# Arduino_MEGA_2560-Rev3.net
KiCad netlist of a schematic drawn in EAGLE
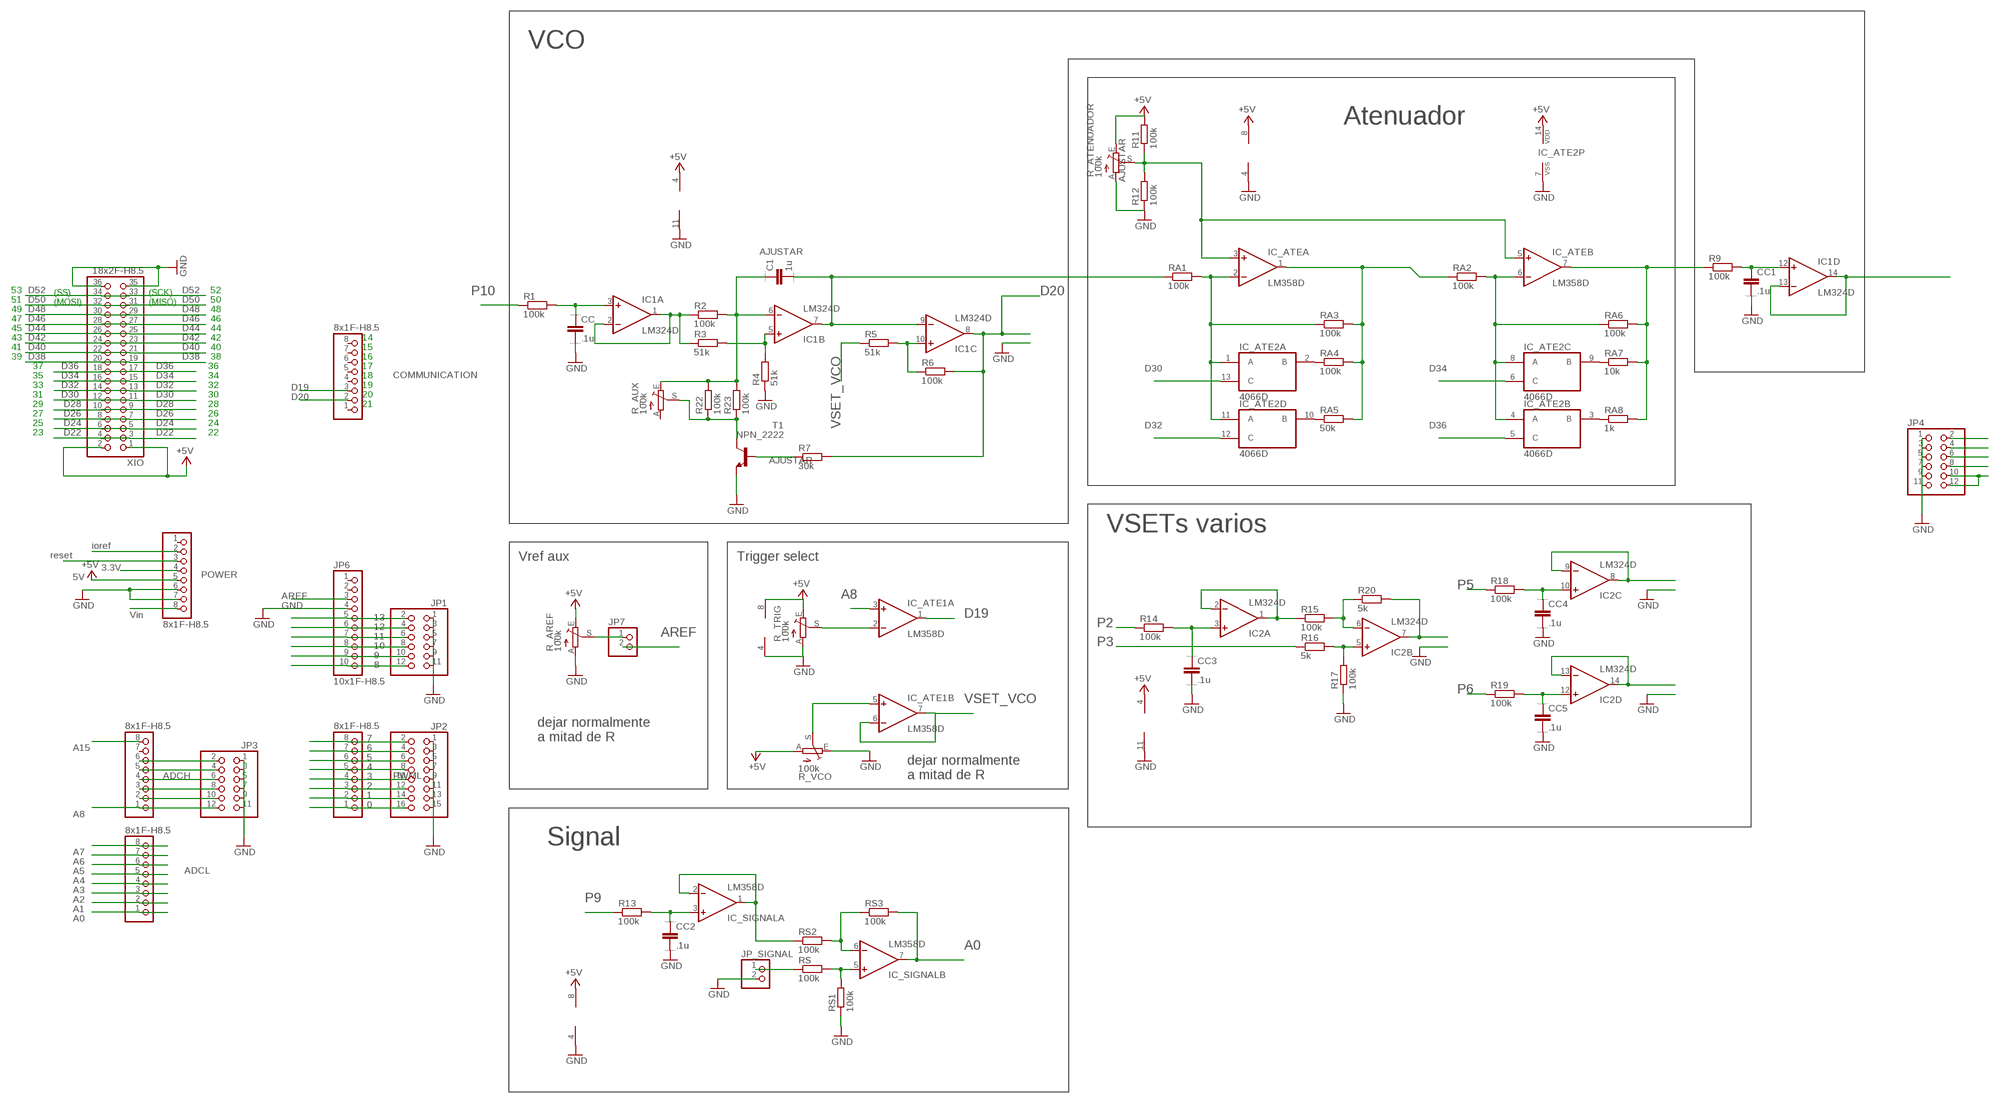
[diagram p0: schematic, sheet 1]

(export (version "E")
  (design (tool "Eeschema 10.0.6"))
  (components
    (comp (ref "ADCH")
      (value "8x1F-H8.5")
      (footprint "eagle-import:1X08")
      (libsource (lib "eagle-import") (part "PINHD-1X8"))
    )
    (comp (ref "ADCL")
      (value "8x1F-H8.5")
      (footprint "eagle-import:1X08")
      (libsource (lib "eagle-import") (part "PINHD-1X8"))
    )
    (comp (ref "C1")
      (value "1u")
      (footprint "eagle-import:C1812")
      (libsource (lib "eagle-import") (part "CC1812"))
    )
    (comp (ref "CC")
      (value ".1u")
      (footprint "eagle-import:C1812")
      (libsource (lib "eagle-import") (part "CC1812"))
    )
    (comp (ref "CC1")
      (value ".1u")
      (footprint "eagle-import:C1812")
      (libsource (lib "eagle-import") (part "CC1812"))
    )
    (comp (ref "CC2")
      (value ".1u")
      (footprint "eagle-import:C1812")
      (libsource (lib "eagle-import") (part "CC1812"))
    )
    (comp (ref "CC3")
      (value ".1u")
      (footprint "eagle-import:C1812")
      (libsource (lib "eagle-import") (part "CC1812"))
    )
    (comp (ref "CC4")
      (value ".1u")
      (footprint "eagle-import:C1812")
      (libsource (lib "eagle-import") (part "CC1812"))
    )
    (comp (ref "CC5")
      (value ".1u")
      (footprint "eagle-import:C1812")
      (libsource (lib "eagle-import") (part "CC1812"))
    )
    (comp (ref "COMMUNICATION")
      (value "8x1F-H8.5")
      (footprint "eagle-import:1X08")
      (libsource (lib "eagle-import") (part "PINHD-1X8"))
    )
    (comp (ref "IC1")
      (value "LM324D")
      (footprint "eagle-import:SO14")
      (libsource (lib "eagle-import") (part "LM324D"))
    )
    (comp (ref "IC2")
      (value "LM324D")
      (footprint "eagle-import:SO14")
      (libsource (lib "eagle-import") (part "LM324D"))
    )
    (comp (ref "IC_ATE")
      (value "LM358D")
      (footprint "eagle-import:SO08")
      (libsource (lib "eagle-import") (part "LM358D"))
    )
    (comp (ref "IC_ATE1")
      (value "LM358D")
      (footprint "eagle-import:SO08")
      (libsource (lib "eagle-import") (part "LM358D"))
    )
    (comp (ref "IC_ATE2")
      (value "4066D")
      (footprint "eagle-import:SO14")
      (libsource (lib "eagle-import") (part "4066D"))
    )
    (comp (ref "IC_SIGNAL")
      (value "LM358D")
      (footprint "eagle-import:SO08")
      (libsource (lib "eagle-import") (part "LM358D"))
    )
    (comp (ref "JP1")
      (value "PINHD-2X6")
      (footprint "eagle-import:2X06")
      (libsource (lib "eagle-import") (part "PINHD-2X6"))
    )
    (comp (ref "JP2")
      (value "PINHD-2X8")
      (footprint "eagle-import:2X08")
      (libsource (lib "eagle-import") (part "PINHD-2X8"))
    )
    (comp (ref "JP3")
      (value "PINHD-2X6")
      (footprint "eagle-import:2X06")
      (libsource (lib "eagle-import") (part "PINHD-2X6"))
    )
    (comp (ref "JP4")
      (value "PINHD-2X6")
      (footprint "eagle-import:2X06")
      (libsource (lib "eagle-import") (part "PINHD-2X6"))
    )
    (comp (ref "JP6")
      (value "10x1F-H8.5")
      (footprint "eagle-import:1X10")
      (libsource (lib "eagle-import") (part "PINHD-1X10_ARD"))
    )
    (comp (ref "JP7")
      (value "PINHD-1X2")
      (footprint "eagle-import:1X02")
      (libsource (lib "eagle-import") (part "PINHD-1X2"))
    )
    (comp (ref "JP_SIGNAL")
      (value "PINHD-1X2")
      (footprint "eagle-import:1X02")
      (libsource (lib "eagle-import") (part "PINHD-1X2"))
    )
    (comp (ref "POWER")
      (value "8x1F-H8.5")
      (footprint "eagle-import:1X08")
      (libsource (lib "eagle-import") (part "PINHD-1X8"))
    )
    (comp (ref "PWML")
      (value "8x1F-H8.5")
      (footprint "eagle-import:1X08")
      (libsource (lib "eagle-import") (part "PINHD-1X8"))
    )
    (comp (ref "R1")
      (value "100k")
      (footprint "eagle-import:R1206")
      (libsource (lib "eagle-import") (part "R-EU_R1206"))
    )
    (comp (ref "R2")
      (value "100k")
      (footprint "eagle-import:R1206")
      (libsource (lib "eagle-import") (part "R-EU_R1206"))
    )
    (comp (ref "R3")
      (value "51k")
      (footprint "eagle-import:R1206")
      (libsource (lib "eagle-import") (part "R-EU_R1206"))
    )
    (comp (ref "R4")
      (value "51k")
      (footprint "eagle-import:R1206")
      (libsource (lib "eagle-import") (part "R-EU_R1206"))
    )
    (comp (ref "R5")
      (value "51k")
      (footprint "eagle-import:R1206")
      (libsource (lib "eagle-import") (part "R-EU_R1206"))
    )
    (comp (ref "R6")
      (value "100k")
      (footprint "eagle-import:R1206")
      (libsource (lib "eagle-import") (part "R-EU_R1206"))
    )
    (comp (ref "R7")
      (value "30k")
      (footprint "eagle-import:0204_7")
      (libsource (lib "eagle-import") (part "R-EU_0204/7"))
    )
    (comp (ref "R9")
      (value "100k")
      (footprint "eagle-import:R1206")
      (libsource (lib "eagle-import") (part "R-EU_R1206"))
    )
    (comp (ref "R11")
      (value "100k")
      (footprint "eagle-import:R1206")
      (libsource (lib "eagle-import") (part "R-EU_R1206"))
    )
    (comp (ref "R12")
      (value "100k")
      (footprint "eagle-import:R1206")
      (libsource (lib "eagle-import") (part "R-EU_R1206"))
    )
    (comp (ref "R13")
      (value "100k")
      (footprint "eagle-import:R1206")
      (libsource (lib "eagle-import") (part "R-EU_R1206"))
    )
    (comp (ref "R14")
      (value "100k")
      (footprint "eagle-import:R1206")
      (libsource (lib "eagle-import") (part "R-EU_R1206"))
    )
    (comp (ref "R15")
      (value "100k")
      (footprint "eagle-import:R1206")
      (libsource (lib "eagle-import") (part "R-EU_R1206"))
    )
    (comp (ref "R16")
      (value "5k")
      (footprint "eagle-import:R1206")
      (libsource (lib "eagle-import") (part "R-EU_R1206"))
    )
    (comp (ref "R17")
      (value "100k")
      (footprint "eagle-import:R1206")
      (libsource (lib "eagle-import") (part "R-EU_R1206"))
    )
    (comp (ref "R18")
      (value "100k")
      (footprint "eagle-import:R1206")
      (libsource (lib "eagle-import") (part "R-EU_R1206"))
    )
    (comp (ref "R19")
      (value "100k")
      (footprint "eagle-import:R1206")
      (libsource (lib "eagle-import") (part "R-EU_R1206"))
    )
    (comp (ref "R20")
      (value "5k")
      (footprint "eagle-import:R1206")
      (libsource (lib "eagle-import") (part "R-EU_R1206"))
    )
    (comp (ref "R22")
      (value "100k")
      (footprint "eagle-import:R1206")
      (libsource (lib "eagle-import") (part "R-EU_R1206"))
    )
    (comp (ref "R23")
      (value "100k")
      (footprint "eagle-import:R1206")
      (libsource (lib "eagle-import") (part "R-EU_R1206"))
    )
    (comp (ref "RA1")
      (value "100k")
      (footprint "eagle-import:R1206")
      (libsource (lib "eagle-import") (part "R-EU_R1206"))
    )
    (comp (ref "RA2")
      (value "100k")
      (footprint "eagle-import:R1206")
      (libsource (lib "eagle-import") (part "R-EU_R1206"))
    )
    (comp (ref "RA3")
      (value "100k")
      (footprint "eagle-import:R1206")
      (libsource (lib "eagle-import") (part "R-EU_R1206"))
    )
    (comp (ref "RA4")
      (value "100k")
      (footprint "eagle-import:R1206")
      (libsource (lib "eagle-import") (part "R-EU_R1206"))
    )
    (comp (ref "RA5")
      (value "50k")
      (footprint "eagle-import:R1206")
      (libsource (lib "eagle-import") (part "R-EU_R1206"))
    )
    (comp (ref "RA6")
      (value "100k")
      (footprint "eagle-import:R1206")
      (libsource (lib "eagle-import") (part "R-EU_R1206"))
    )
    (comp (ref "RA7")
      (value "10k")
      (footprint "eagle-import:0204_7")
      (libsource (lib "eagle-import") (part "R-EU_0204/7"))
    )
    (comp (ref "RA8")
      (value "1k")
      (footprint "eagle-import:0204_7")
      (libsource (lib "eagle-import") (part "R-EU_0204/7"))
    )
    (comp (ref "RS")
      (value "100k")
      (footprint "eagle-import:R1206")
      (libsource (lib "eagle-import") (part "R-EU_R1206"))
    )
    (comp (ref "RS1")
      (value "100k")
      (footprint "eagle-import:R1206")
      (libsource (lib "eagle-import") (part "R-EU_R1206"))
    )
    (comp (ref "RS2")
      (value "100k")
      (footprint "eagle-import:R1206")
      (libsource (lib "eagle-import") (part "R-EU_R1206"))
    )
    (comp (ref "RS3")
      (value "100k")
      (footprint "eagle-import:R1206")
      (libsource (lib "eagle-import") (part "R-EU_R1206"))
    )
    (comp (ref "R_AREF")
      (value "100k")
      (footprint "eagle-import:B64Y")
      (libsource (lib "eagle-import") (part "TRIM_EU-B64Y"))
    )
    (comp (ref "R_ATENUADOR")
      (value "100k")
      (footprint "eagle-import:B64Y")
      (libsource (lib "eagle-import") (part "TRIM_EU-B64Y"))
    )
    (comp (ref "R_AUX")
      (value "100k")
      (footprint "eagle-import:B64Y")
      (libsource (lib "eagle-import") (part "TRIM_EU-B64Y"))
    )
    (comp (ref "R_TRIG")
      (value "100k")
      (footprint "eagle-import:B64Y")
      (libsource (lib "eagle-import") (part "TRIM_EU-B64Y"))
    )
    (comp (ref "R_VCO")
      (value "100k")
      (footprint "eagle-import:B64Y")
      (libsource (lib "eagle-import") (part "TRIM_EU-B64Y"))
    )
    (comp (ref "T1")
      (value "NPN_2222")
      (footprint "eagle-import:TO19_SUP")
      (libsource (lib "eagle-import") (part "NPN_SUP"))
    )
    (comp (ref "XIO")
      (value "18x2F-H8.5")
      (footprint "eagle-import:2X18")
      (libsource (lib "eagle-import") (part "PINHD-2X18"))
    )
  )
  (nets
    (net (code "1") (name "+5V") (class "Default")
      (node (ref "IC1") (pin "4") (pinfunction "V+_4") (pintype "power_in"))
      (node (ref "IC2") (pin "4") (pinfunction "V+_4") (pintype "power_in"))
      (node (ref "IC_ATE") (pin "8") (pinfunction "V+_8") (pintype "power_in"))
      (node (ref "IC_ATE1") (pin "8") (pinfunction "V+_8") (pintype "power_in"))
      (node (ref "IC_ATE2") (pin "14") (pinfunction "VDD_14") (pintype "power_in"))
      (node (ref "IC_SIGNAL") (pin "8") (pinfunction "V+_8") (pintype "power_in"))
      (node (ref "POWER") (pin "5") (pinfunction "5_5") (pintype "passive"))
      (node (ref "R11") (pin "2") (pinfunction "2_2") (pintype "passive"))
      (node (ref "R_AREF") (pin "E") (pinfunction "E_E") (pintype "passive"))
      (node (ref "R_ATENUADOR") (pin "E") (pinfunction "E_E") (pintype "passive"))
      (node (ref "R_TRIG") (pin "E") (pinfunction "E_E") (pintype "passive"))
      (node (ref "R_VCO") (pin "A") (pinfunction "A_A") (pintype "passive"))
      (node (ref "XIO") (pin "1") (pinfunction "1_1") (pintype "passive"))
      (node (ref "XIO") (pin "2") (pinfunction "2_2") (pintype "passive"))
    )
    (net (code "2") (name "/A0") (class "Default")
      (node (ref "ADCL") (pin "1") (pinfunction "1_1") (pintype "passive"))
      (node (ref "IC_SIGNAL") (pin "7") (pinfunction "OUT_7") (pintype "output"))
      (node (ref "RS3") (pin "2") (pinfunction "2_2") (pintype "passive"))
    )
    (net (code "3") (name "/A8") (class "Default")
      (node (ref "ADCH") (pin "1") (pinfunction "1_1") (pintype "passive"))
      (node (ref "IC_ATE1") (pin "3") (pinfunction "+IN_3") (pintype "input"))
      (node (ref "JP3") (pin "12") (pinfunction "12_12") (pintype "passive"))
    )
    (net (code "4") (name "/AREF") (class "Default")
      (node (ref "JP6") (pin "3") (pinfunction "3_3") (pintype "passive"))
      (node (ref "JP7") (pin "2") (pinfunction "2_2") (pintype "passive"))
    )
    (net (code "5") (name "/D19") (class "Default")
      (node (ref "COMMUNICATION") (pin "3") (pinfunction "3_3") (pintype "passive"))
      (node (ref "IC_ATE1") (pin "1") (pinfunction "OUT_1") (pintype "output"))
    )
    (net (code "6") (name "/D20") (class "Default")
      (node (ref "COMMUNICATION") (pin "2") (pinfunction "2_2") (pintype "passive"))
      (node (ref "IC1") (pin "8") (pinfunction "OUT_8") (pintype "output"))
      (node (ref "JP4") (pin "2") (pinfunction "2_2") (pintype "passive"))
      (node (ref "R6") (pin "2") (pinfunction "2_2") (pintype "passive"))
      (node (ref "R7") (pin "2") (pinfunction "2_2") (pintype "passive"))
    )
    (net (code "7") (name "/D22") (class "Default")
      (node (ref "XIO") (pin "3") (pinfunction "3_3") (pintype "passive"))
      (node (ref "XIO") (pin "4") (pinfunction "4_4") (pintype "passive"))
    )
    (net (code "8") (name "/D24") (class "Default")
      (node (ref "XIO") (pin "5") (pinfunction "5_5") (pintype "passive"))
      (node (ref "XIO") (pin "6") (pinfunction "6_6") (pintype "passive"))
    )
    (net (code "9") (name "/D26") (class "Default")
      (node (ref "XIO") (pin "7") (pinfunction "7_7") (pintype "passive"))
      (node (ref "XIO") (pin "8") (pinfunction "8_8") (pintype "passive"))
    )
    (net (code "10") (name "/D28") (class "Default")
      (node (ref "XIO") (pin "10") (pinfunction "10_10") (pintype "passive"))
      (node (ref "XIO") (pin "9") (pinfunction "9_9") (pintype "passive"))
    )
    (net (code "11") (name "/D30") (class "Default")
      (node (ref "IC_ATE2") (pin "13") (pinfunction "C_13") (pintype "input"))
      (node (ref "XIO") (pin "11") (pinfunction "11_11") (pintype "passive"))
      (node (ref "XIO") (pin "12") (pinfunction "12_12") (pintype "passive"))
    )
    (net (code "12") (name "/D32") (class "Default")
      (node (ref "IC_ATE2") (pin "12") (pinfunction "C_12") (pintype "input"))
      (node (ref "XIO") (pin "13") (pinfunction "13_13") (pintype "passive"))
      (node (ref "XIO") (pin "14") (pinfunction "14_14") (pintype "passive"))
    )
    (net (code "13") (name "/D34") (class "Default")
      (node (ref "IC_ATE2") (pin "6") (pinfunction "C_6") (pintype "input"))
      (node (ref "XIO") (pin "15") (pinfunction "15_15") (pintype "passive"))
      (node (ref "XIO") (pin "16") (pinfunction "16_16") (pintype "passive"))
    )
    (net (code "14") (name "/D36") (class "Default")
      (node (ref "IC_ATE2") (pin "5") (pinfunction "C_5") (pintype "input"))
      (node (ref "XIO") (pin "17") (pinfunction "17_17") (pintype "passive"))
      (node (ref "XIO") (pin "18") (pinfunction "18_18") (pintype "passive"))
    )
    (net (code "15") (name "/D38") (class "Default")
      (node (ref "XIO") (pin "19") (pinfunction "19_19") (pintype "passive"))
      (node (ref "XIO") (pin "20") (pinfunction "20_20") (pintype "passive"))
    )
    (net (code "16") (name "/D40") (class "Default")
      (node (ref "XIO") (pin "21") (pinfunction "21_21") (pintype "passive"))
      (node (ref "XIO") (pin "22") (pinfunction "22_22") (pintype "passive"))
    )
    (net (code "17") (name "/D42") (class "Default")
      (node (ref "XIO") (pin "23") (pinfunction "23_23") (pintype "passive"))
      (node (ref "XIO") (pin "24") (pinfunction "24_24") (pintype "passive"))
    )
    (net (code "18") (name "/D44") (class "Default")
      (node (ref "XIO") (pin "25") (pinfunction "25_25") (pintype "passive"))
      (node (ref "XIO") (pin "26") (pinfunction "26_26") (pintype "passive"))
    )
    (net (code "19") (name "/D46") (class "Default")
      (node (ref "XIO") (pin "27") (pinfunction "27_27") (pintype "passive"))
      (node (ref "XIO") (pin "28") (pinfunction "28_28") (pintype "passive"))
    )
    (net (code "20") (name "/D48") (class "Default")
      (node (ref "XIO") (pin "29") (pinfunction "29_29") (pintype "passive"))
      (node (ref "XIO") (pin "30") (pinfunction "30_30") (pintype "passive"))
    )
    (net (code "21") (name "/D50") (class "Default")
      (node (ref "XIO") (pin "31") (pinfunction "31_31") (pintype "passive"))
      (node (ref "XIO") (pin "32") (pinfunction "32_32") (pintype "passive"))
    )
    (net (code "22") (name "/D52") (class "Default")
      (node (ref "XIO") (pin "33") (pinfunction "33_33") (pintype "passive"))
      (node (ref "XIO") (pin "34") (pinfunction "34_34") (pintype "passive"))
    )
    (net (code "23") (name "/P2") (class "Default")
      (node (ref "JP2") (pin "12") (pinfunction "12_12") (pintype "passive"))
      (node (ref "PWML") (pin "3") (pinfunction "3_3") (pintype "passive"))
      (node (ref "R14") (pin "1") (pinfunction "1_1") (pintype "passive"))
    )
    (net (code "24") (name "/P3") (class "Default")
      (node (ref "JP2") (pin "10") (pinfunction "10_10") (pintype "passive"))
      (node (ref "PWML") (pin "4") (pinfunction "4_4") (pintype "passive"))
      (node (ref "R16") (pin "1") (pinfunction "1_1") (pintype "passive"))
    )
    (net (code "25") (name "/P5") (class "Default")
      (node (ref "JP2") (pin "6") (pinfunction "6_6") (pintype "passive"))
      (node (ref "PWML") (pin "6") (pinfunction "6_6") (pintype "passive"))
      (node (ref "R18") (pin "1") (pinfunction "1_1") (pintype "passive"))
    )
    (net (code "26") (name "/P6") (class "Default")
      (node (ref "JP2") (pin "4") (pinfunction "4_4") (pintype "passive"))
      (node (ref "PWML") (pin "7") (pinfunction "7_7") (pintype "passive"))
      (node (ref "R19") (pin "1") (pinfunction "1_1") (pintype "passive"))
    )
    (net (code "27") (name "/P9") (class "Default")
      (node (ref "JP1") (pin "10") (pinfunction "10_10") (pintype "passive"))
      (node (ref "JP6") (pin "9") (pinfunction "9_9") (pintype "passive"))
      (node (ref "R13") (pin "1") (pinfunction "1_1") (pintype "passive"))
    )
    (net (code "28") (name "/P10") (class "Default")
      (node (ref "JP1") (pin "8") (pinfunction "8_8") (pintype "passive"))
      (node (ref "JP6") (pin "8") (pinfunction "8_8") (pintype "passive"))
      (node (ref "R1") (pin "1") (pinfunction "1_1") (pintype "passive"))
    )
    (net (code "29") (name "/SP5") (class "Default")
      (node (ref "IC2") (pin "8") (pinfunction "OUT_8") (pintype "output"))
      (node (ref "IC2") (pin "9") (pinfunction "-IN_9") (pintype "input"))
      (node (ref "JP4") (pin "4") (pinfunction "4_4") (pintype "passive"))
    )
    (net (code "30") (name "/SP6") (class "Default")
      (node (ref "IC2") (pin "13") (pinfunction "-IN_13") (pintype "input"))
      (node (ref "IC2") (pin "14") (pinfunction "OUT_14") (pintype "output"))
      (node (ref "JP4") (pin "6") (pinfunction "6_6") (pintype "passive"))
    )
    (net (code "31") (name "/SPSUPER") (class "Default")
      (node (ref "IC2") (pin "7") (pinfunction "OUT_7") (pintype "output"))
      (node (ref "JP4") (pin "8") (pinfunction "8_8") (pintype "passive"))
      (node (ref "R20") (pin "2") (pinfunction "2_2") (pintype "passive"))
    )
    (net (code "32") (name "/TRIANG_ATE") (class "Default")
      (node (ref "IC1") (pin "13") (pinfunction "-IN_13") (pintype "input"))
      (node (ref "IC1") (pin "14") (pinfunction "OUT_14") (pintype "output"))
      (node (ref "JP4") (pin "10") (pinfunction "10_10") (pintype "passive"))
      (node (ref "JP4") (pin "12") (pinfunction "12_12") (pintype "passive"))
    )
    (net (code "33") (name "/VSET_VCO") (class "Default")
      (node (ref "IC_ATE1") (pin "6") (pinfunction "-IN_6") (pintype "input"))
      (node (ref "IC_ATE1") (pin "7") (pinfunction "OUT_7") (pintype "output"))
      (node (ref "R5") (pin "1") (pinfunction "1_1") (pintype "passive"))
    )
    (net (code "34") (name "GND") (class "Default")
      (node (ref "CC") (pin "2") (pinfunction "2_2") (pintype "passive"))
      (node (ref "CC1") (pin "2") (pinfunction "2_2") (pintype "passive"))
      (node (ref "CC2") (pin "2") (pinfunction "2_2") (pintype "passive"))
      (node (ref "CC3") (pin "2") (pinfunction "2_2") (pintype "passive"))
      (node (ref "CC4") (pin "2") (pinfunction "2_2") (pintype "passive"))
      (node (ref "CC5") (pin "2") (pinfunction "2_2") (pintype "passive"))
      (node (ref "IC1") (pin "11") (pinfunction "V-_11") (pintype "power_in"))
      (node (ref "IC2") (pin "11") (pinfunction "V-_11") (pintype "power_in"))
      (node (ref "IC_ATE") (pin "4") (pinfunction "V-_4") (pintype "power_in"))
      (node (ref "IC_ATE1") (pin "4") (pinfunction "V-_4") (pintype "power_in"))
      (node (ref "IC_ATE2") (pin "7") (pinfunction "VSS_7") (pintype "power_in"))
      (node (ref "IC_SIGNAL") (pin "4") (pinfunction "V-_4") (pintype "power_in"))
      (node (ref "JP1") (pin "1") (pinfunction "1_1") (pintype "passive"))
      (node (ref "JP1") (pin "11") (pinfunction "11_11") (pintype "passive"))
      (node (ref "JP1") (pin "3") (pinfunction "3_3") (pintype "passive"))
      (node (ref "JP1") (pin "5") (pinfunction "5_5") (pintype "passive"))
      (node (ref "JP1") (pin "7") (pinfunction "7_7") (pintype "passive"))
      (node (ref "JP1") (pin "9") (pinfunction "9_9") (pintype "passive"))
      (node (ref "JP2") (pin "1") (pinfunction "1_1") (pintype "passive"))
      (node (ref "JP2") (pin "11") (pinfunction "11_11") (pintype "passive"))
      (node (ref "JP2") (pin "13") (pinfunction "13_13") (pintype "passive"))
      (node (ref "JP2") (pin "15") (pinfunction "15_15") (pintype "passive"))
      (node (ref "JP2") (pin "3") (pinfunction "3_3") (pintype "passive"))
      (node (ref "JP2") (pin "5") (pinfunction "5_5") (pintype "passive"))
      (node (ref "JP2") (pin "7") (pinfunction "7_7") (pintype "passive"))
      (node (ref "JP2") (pin "9") (pinfunction "9_9") (pintype "passive"))
      (node (ref "JP3") (pin "1") (pinfunction "1_1") (pintype "passive"))
      (node (ref "JP3") (pin "11") (pinfunction "11_11") (pintype "passive"))
      (node (ref "JP3") (pin "3") (pinfunction "3_3") (pintype "passive"))
      (node (ref "JP3") (pin "5") (pinfunction "5_5") (pintype "passive"))
      (node (ref "JP3") (pin "7") (pinfunction "7_7") (pintype "passive"))
      (node (ref "JP3") (pin "9") (pinfunction "9_9") (pintype "passive"))
      (node (ref "JP4") (pin "1") (pinfunction "1_1") (pintype "passive"))
      (node (ref "JP4") (pin "11") (pinfunction "11_11") (pintype "passive"))
      (node (ref "JP4") (pin "3") (pinfunction "3_3") (pintype "passive"))
      (node (ref "JP4") (pin "5") (pinfunction "5_5") (pintype "passive"))
      (node (ref "JP4") (pin "7") (pinfunction "7_7") (pintype "passive"))
      (node (ref "JP4") (pin "9") (pinfunction "9_9") (pintype "passive"))
      (node (ref "JP6") (pin "4") (pinfunction "4_4") (pintype "passive"))
      (node (ref "JP_SIGNAL") (pin "2") (pinfunction "2_2") (pintype "passive"))
      (node (ref "POWER") (pin "6") (pinfunction "6_6") (pintype "passive"))
      (node (ref "POWER") (pin "7") (pinfunction "7_7") (pintype "passive"))
      (node (ref "R12") (pin "1") (pinfunction "1_1") (pintype "passive"))
      (node (ref "R17") (pin "1") (pinfunction "1_1") (pintype "passive"))
      (node (ref "R4") (pin "1") (pinfunction "1_1") (pintype "passive"))
      (node (ref "RS1") (pin "1") (pinfunction "1_1") (pintype "passive"))
      (node (ref "R_AREF") (pin "A") (pinfunction "A_A") (pintype "passive"))
      (node (ref "R_ATENUADOR") (pin "A") (pinfunction "A_A") (pintype "passive"))
      (node (ref "R_TRIG") (pin "A") (pinfunction "A_A") (pintype "passive"))
      (node (ref "R_VCO") (pin "E") (pinfunction "E_E") (pintype "passive"))
      (node (ref "T1") (pin "3") (pinfunction "E_3") (pintype "passive"))
      (node (ref "XIO") (pin "35") (pinfunction "35_35") (pintype "passive"))
      (node (ref "XIO") (pin "36") (pinfunction "36_36") (pintype "passive"))
    )
    (net (code "35") (name "Net-(ADCH-Pad2)") (class "Default")
      (node (ref "ADCH") (pin "2") (pinfunction "2_2") (pintype "passive"))
      (node (ref "JP3") (pin "10") (pinfunction "10_10") (pintype "passive"))
    )
    (net (code "36") (name "Net-(ADCH-Pad3)") (class "Default")
      (node (ref "ADCH") (pin "3") (pinfunction "3_3") (pintype "passive"))
      (node (ref "JP3") (pin "8") (pinfunction "8_8") (pintype "passive"))
    )
    (net (code "37") (name "Net-(ADCH-Pad4)") (class "Default")
      (node (ref "ADCH") (pin "4") (pinfunction "4_4") (pintype "passive"))
      (node (ref "JP3") (pin "6") (pinfunction "6_6") (pintype "passive"))
    )
    (net (code "38") (name "Net-(ADCH-Pad5)") (class "Default")
      (node (ref "ADCH") (pin "5") (pinfunction "5_5") (pintype "passive"))
      (node (ref "JP3") (pin "4") (pinfunction "4_4") (pintype "passive"))
    )
    (net (code "39") (name "Net-(ADCH-Pad6)") (class "Default")
      (node (ref "ADCH") (pin "6") (pinfunction "6_6") (pintype "passive"))
      (node (ref "JP3") (pin "2") (pinfunction "2_2") (pintype "passive"))
    )
    (net (code "40") (name "Net-(IC1A-+IN)") (class "Default")
      (node (ref "CC") (pin "1") (pinfunction "1_1") (pintype "passive"))
      (node (ref "IC1") (pin "3") (pinfunction "+IN_3") (pintype "input"))
      (node (ref "R1") (pin "2") (pinfunction "2_2") (pintype "passive"))
    )
    (net (code "41") (name "Net-(IC1A--IN)") (class "Default")
      (node (ref "IC1") (pin "1") (pinfunction "OUT_1") (pintype "output"))
      (node (ref "IC1") (pin "2") (pinfunction "-IN_2") (pintype "input"))
      (node (ref "R2") (pin "1") (pinfunction "1_1") (pintype "passive"))
      (node (ref "R3") (pin "1") (pinfunction "1_1") (pintype "passive"))
    )
    (net (code "42") (name "Net-(IC1B-+IN)") (class "Default")
      (node (ref "IC1") (pin "5") (pinfunction "+IN_5") (pintype "input"))
      (node (ref "R3") (pin "2") (pinfunction "2_2") (pintype "passive"))
      (node (ref "R4") (pin "2") (pinfunction "2_2") (pintype "passive"))
    )
    (net (code "43") (name "Net-(IC1B--IN)") (class "Default")
      (node (ref "C1") (pin "1") (pinfunction "1_1") (pintype "passive"))
      (node (ref "IC1") (pin "6") (pinfunction "-IN_6") (pintype "input"))
      (node (ref "R2") (pin "2") (pinfunction "2_2") (pintype "passive"))
      (node (ref "R22") (pin "2") (pinfunction "2_2") (pintype "passive"))
      (node (ref "R23") (pin "2") (pinfunction "2_2") (pintype "passive"))
      (node (ref "R_AUX") (pin "E") (pinfunction "E_E") (pintype "passive"))
    )
    (net (code "44") (name "Net-(IC1B-OUT)") (class "Default")
      (node (ref "C1") (pin "2") (pinfunction "2_2") (pintype "passive"))
      (node (ref "IC1") (pin "7") (pinfunction "OUT_7") (pintype "output"))
      (node (ref "IC1") (pin "9") (pinfunction "-IN_9") (pintype "input"))
      (node (ref "RA1") (pin "1") (pinfunction "1_1") (pintype "passive"))
    )
    (net (code "45") (name "Net-(IC1C-+IN)") (class "Default")
      (node (ref "IC1") (pin "10") (pinfunction "+IN_10") (pintype "input"))
      (node (ref "R5") (pin "2") (pinfunction "2_2") (pintype "passive"))
      (node (ref "R6") (pin "1") (pinfunction "1_1") (pintype "passive"))
    )
    (net (code "46") (name "Net-(IC1D-+IN)") (class "Default")
      (node (ref "CC1") (pin "1") (pinfunction "1_1") (pintype "passive"))
      (node (ref "IC1") (pin "12") (pinfunction "+IN_12") (pintype "input"))
      (node (ref "R9") (pin "2") (pinfunction "2_2") (pintype "passive"))
    )
    (net (code "47") (name "Net-(IC2A-+IN)") (class "Default")
      (node (ref "CC3") (pin "1") (pinfunction "1_1") (pintype "passive"))
      (node (ref "IC2") (pin "3") (pinfunction "+IN_3") (pintype "input"))
      (node (ref "R14") (pin "2") (pinfunction "2_2") (pintype "passive"))
    )
    (net (code "48") (name "Net-(IC2A--IN)") (class "Default")
      (node (ref "IC2") (pin "1") (pinfunction "OUT_1") (pintype "output"))
      (node (ref "IC2") (pin "2") (pinfunction "-IN_2") (pintype "input"))
      (node (ref "R15") (pin "1") (pinfunction "1_1") (pintype "passive"))
    )
    (net (code "49") (name "Net-(IC2B-+IN)") (class "Default")
      (node (ref "IC2") (pin "5") (pinfunction "+IN_5") (pintype "input"))
      (node (ref "R16") (pin "2") (pinfunction "2_2") (pintype "passive"))
      (node (ref "R17") (pin "2") (pinfunction "2_2") (pintype "passive"))
    )
    (net (code "50") (name "Net-(IC2B--IN)") (class "Default")
      (node (ref "IC2") (pin "6") (pinfunction "-IN_6") (pintype "input"))
      (node (ref "R15") (pin "2") (pinfunction "2_2") (pintype "passive"))
      (node (ref "R20") (pin "1") (pinfunction "1_1") (pintype "passive"))
    )
    (net (code "51") (name "Net-(IC2C-+IN)") (class "Default")
      (node (ref "CC4") (pin "1") (pinfunction "1_1") (pintype "passive"))
      (node (ref "IC2") (pin "10") (pinfunction "+IN_10") (pintype "input"))
      (node (ref "R18") (pin "2") (pinfunction "2_2") (pintype "passive"))
    )
    (net (code "52") (name "Net-(IC2D-+IN)") (class "Default")
      (node (ref "CC5") (pin "1") (pinfunction "1_1") (pintype "passive"))
      (node (ref "IC2") (pin "12") (pinfunction "+IN_12") (pintype "input"))
      (node (ref "R19") (pin "2") (pinfunction "2_2") (pintype "passive"))
    )
    (net (code "53") (name "Net-(IC_ATE1A--IN)") (class "Default")
      (node (ref "IC_ATE1") (pin "2") (pinfunction "-IN_2") (pintype "input"))
      (node (ref "R_TRIG") (pin "S") (pinfunction "S_S") (pintype "passive"))
    )
    (net (code "54") (name "Net-(IC_ATE1B-+IN)") (class "Default")
      (node (ref "IC_ATE1") (pin "5") (pinfunction "+IN_5") (pintype "input"))
      (node (ref "R_VCO") (pin "S") (pinfunction "S_S") (pintype "passive"))
    )
    (net (code "55") (name "Net-(IC_ATE2A-A)") (class "Default")
      (node (ref "IC_ATE") (pin "2") (pinfunction "-IN_2") (pintype "input"))
      (node (ref "IC_ATE2") (pin "1") (pinfunction "A_1") (pintype "tri_state"))
      (node (ref "IC_ATE2") (pin "11") (pinfunction "A_11") (pintype "tri_state"))
      (node (ref "RA1") (pin "2") (pinfunction "2_2") (pintype "passive"))
      (node (ref "RA3") (pin "1") (pinfunction "1_1") (pintype "passive"))
    )
    (net (code "56") (name "Net-(IC_ATE2A-B)") (class "Default")
      (node (ref "IC_ATE2") (pin "2") (pinfunction "B_2") (pintype "tri_state"))
      (node (ref "RA4") (pin "1") (pinfunction "1_1") (pintype "passive"))
    )
    (net (code "57") (name "Net-(IC_ATE2B-A)") (class "Default")
      (node (ref "IC_ATE") (pin "6") (pinfunction "-IN_6") (pintype "input"))
      (node (ref "IC_ATE2") (pin "4") (pinfunction "A_4") (pintype "tri_state"))
      (node (ref "IC_ATE2") (pin "8") (pinfunction "A_8") (pintype "tri_state"))
      (node (ref "RA2") (pin "2") (pinfunction "2_2") (pintype "passive"))
      (node (ref "RA6") (pin "1") (pinfunction "1_1") (pintype "passive"))
    )
    (net (code "58") (name "Net-(IC_ATE2B-B)") (class "Default")
      (node (ref "IC_ATE2") (pin "3") (pinfunction "B_3") (pintype "tri_state"))
      (node (ref "RA8") (pin "1") (pinfunction "1_1") (pintype "passive"))
    )
    (net (code "59") (name "Net-(IC_ATE2C-B)") (class "Default")
      (node (ref "IC_ATE2") (pin "9") (pinfunction "B_9") (pintype "tri_state"))
      (node (ref "RA7") (pin "1") (pinfunction "1_1") (pintype "passive"))
    )
    (net (code "60") (name "Net-(IC_ATE2D-B)") (class "Default")
      (node (ref "IC_ATE2") (pin "10") (pinfunction "B_10") (pintype "tri_state"))
      (node (ref "RA5") (pin "1") (pinfunction "1_1") (pintype "passive"))
    )
    (net (code "61") (name "Net-(IC_ATEA-+IN)") (class "Default")
      (node (ref "IC_ATE") (pin "3") (pinfunction "+IN_3") (pintype "input"))
      (node (ref "IC_ATE") (pin "5") (pinfunction "+IN_5") (pintype "input"))
      (node (ref "R11") (pin "1") (pinfunction "1_1") (pintype "passive"))
      (node (ref "R12") (pin "2") (pinfunction "2_2") (pintype "passive"))
      (node (ref "R_ATENUADOR") (pin "S") (pinfunction "S_S") (pintype "passive"))
    )
    (net (code "62") (name "Net-(IC_ATEA-OUT)") (class "Default")
      (node (ref "IC_ATE") (pin "1") (pinfunction "OUT_1") (pintype "output"))
      (node (ref "RA2") (pin "1") (pinfunction "1_1") (pintype "passive"))
      (node (ref "RA3") (pin "2") (pinfunction "2_2") (pintype "passive"))
      (node (ref "RA4") (pin "2") (pinfunction "2_2") (pintype "passive"))
      (node (ref "RA5") (pin "2") (pinfunction "2_2") (pintype "passive"))
    )
    (net (code "63") (name "Net-(IC_ATEB-OUT)") (class "Default")
      (node (ref "IC_ATE") (pin "7") (pinfunction "OUT_7") (pintype "output"))
      (node (ref "R9") (pin "1") (pinfunction "1_1") (pintype "passive"))
      (node (ref "RA6") (pin "2") (pinfunction "2_2") (pintype "passive"))
      (node (ref "RA7") (pin "2") (pinfunction "2_2") (pintype "passive"))
      (node (ref "RA8") (pin "2") (pinfunction "2_2") (pintype "passive"))
    )
    (net (code "64") (name "Net-(IC_SIGNALA-+IN)") (class "Default")
      (node (ref "CC2") (pin "1") (pinfunction "1_1") (pintype "passive"))
      (node (ref "IC_SIGNAL") (pin "3") (pinfunction "+IN_3") (pintype "input"))
      (node (ref "R13") (pin "2") (pinfunction "2_2") (pintype "passive"))
    )
    (net (code "65") (name "Net-(IC_SIGNALA--IN)") (class "Default")
      (node (ref "IC_SIGNAL") (pin "1") (pinfunction "OUT_1") (pintype "output"))
      (node (ref "IC_SIGNAL") (pin "2") (pinfunction "-IN_2") (pintype "input"))
      (node (ref "RS2") (pin "1") (pinfunction "1_1") (pintype "passive"))
    )
    (net (code "66") (name "Net-(IC_SIGNALB-+IN)") (class "Default")
      (node (ref "IC_SIGNAL") (pin "5") (pinfunction "+IN_5") (pintype "input"))
      (node (ref "RS") (pin "2") (pinfunction "2_2") (pintype "passive"))
      (node (ref "RS1") (pin "2") (pinfunction "2_2") (pintype "passive"))
    )
    (net (code "67") (name "Net-(IC_SIGNALB--IN)") (class "Default")
      (node (ref "IC_SIGNAL") (pin "6") (pinfunction "-IN_6") (pintype "input"))
      (node (ref "RS2") (pin "2") (pinfunction "2_2") (pintype "passive"))
      (node (ref "RS3") (pin "1") (pinfunction "1_1") (pintype "passive"))
    )
    (net (code "68") (name "Net-(JP1-Pad2)") (class "Default")
      (node (ref "JP1") (pin "2") (pinfunction "2_2") (pintype "passive"))
      (node (ref "JP6") (pin "5") (pinfunction "5_5") (pintype "passive"))
    )
    (net (code "69") (name "Net-(JP1-Pad4)") (class "Default")
      (node (ref "JP1") (pin "4") (pinfunction "4_4") (pintype "passive"))
      (node (ref "JP6") (pin "6") (pinfunction "6_6") (pintype "passive"))
    )
    (net (code "70") (name "Net-(JP1-Pad6)") (class "Default")
      (node (ref "JP1") (pin "6") (pinfunction "6_6") (pintype "passive"))
      (node (ref "JP6") (pin "7") (pinfunction "7_7") (pintype "passive"))
    )
    (net (code "71") (name "Net-(JP1-Pad12)") (class "Default")
      (node (ref "JP1") (pin "12") (pinfunction "12_12") (pintype "passive"))
      (node (ref "JP6") (pin "10") (pinfunction "10_10") (pintype "passive"))
    )
    (net (code "72") (name "Net-(JP2-Pad2)") (class "Default")
      (node (ref "JP2") (pin "2") (pinfunction "2_2") (pintype "passive"))
      (node (ref "PWML") (pin "8") (pinfunction "8_8") (pintype "passive"))
    )
    (net (code "73") (name "Net-(JP2-Pad8)") (class "Default")
      (node (ref "JP2") (pin "8") (pinfunction "8_8") (pintype "passive"))
      (node (ref "PWML") (pin "5") (pinfunction "5_5") (pintype "passive"))
    )
    (net (code "74") (name "Net-(JP2-Pad14)") (class "Default")
      (node (ref "JP2") (pin "14") (pinfunction "14_14") (pintype "passive"))
      (node (ref "PWML") (pin "2") (pinfunction "2_2") (pintype "passive"))
    )
    (net (code "75") (name "Net-(JP2-Pad16)") (class "Default")
      (node (ref "JP2") (pin "16") (pinfunction "16_16") (pintype "passive"))
      (node (ref "PWML") (pin "1") (pinfunction "1_1") (pintype "passive"))
    )
    (net (code "76") (name "Net-(JP7-Pad1)") (class "Default")
      (node (ref "JP7") (pin "1") (pinfunction "1_1") (pintype "passive"))
      (node (ref "R_AREF") (pin "S") (pinfunction "S_S") (pintype "passive"))
    )
    (net (code "77") (name "Net-(JP_SIGNAL-Pad1)") (class "Default")
      (node (ref "JP_SIGNAL") (pin "1") (pinfunction "1_1") (pintype "passive"))
      (node (ref "RS") (pin "1") (pinfunction "1_1") (pintype "passive"))
    )
    (net (code "78") (name "Net-(T1-B)") (class "Default")
      (node (ref "R7") (pin "1") (pinfunction "1_1") (pintype "passive"))
      (node (ref "T1") (pin "2") (pinfunction "B_2") (pintype "passive"))
    )
    (net (code "79") (name "Net-(T1-C)") (class "Default")
      (node (ref "R22") (pin "1") (pinfunction "1_1") (pintype "passive"))
      (node (ref "R23") (pin "1") (pinfunction "1_1") (pintype "passive"))
      (node (ref "R_AUX") (pin "S") (pinfunction "S_S") (pintype "passive"))
      (node (ref "T1") (pin "1") (pinfunction "C_1") (pintype "passive"))
    )
    (net (code "80") (name "unconnected-(ADCH-Pad7)") (class "Default")
      (node (ref "ADCH") (pin "7") (pinfunction "7_7") (pintype "passive"))
    )
    (net (code "81") (name "unconnected-(ADCH-Pad8)") (class "Default")
      (node (ref "ADCH") (pin "8") (pinfunction "8_8") (pintype "passive"))
    )
    (net (code "82") (name "unconnected-(ADCL-Pad2)") (class "Default")
      (node (ref "ADCL") (pin "2") (pinfunction "2_2") (pintype "passive"))
    )
    (net (code "83") (name "unconnected-(ADCL-Pad3)") (class "Default")
      (node (ref "ADCL") (pin "3") (pinfunction "3_3") (pintype "passive"))
    )
    (net (code "84") (name "unconnected-(ADCL-Pad4)") (class "Default")
      (node (ref "ADCL") (pin "4") (pinfunction "4_4") (pintype "passive"))
    )
    (net (code "85") (name "unconnected-(ADCL-Pad5)") (class "Default")
      (node (ref "ADCL") (pin "5") (pinfunction "5_5") (pintype "passive"))
    )
    (net (code "86") (name "unconnected-(ADCL-Pad6)") (class "Default")
      (node (ref "ADCL") (pin "6") (pinfunction "6_6") (pintype "passive"))
    )
    (net (code "87") (name "unconnected-(ADCL-Pad7)") (class "Default")
      (node (ref "ADCL") (pin "7") (pinfunction "7_7") (pintype "passive"))
    )
    (net (code "88") (name "unconnected-(ADCL-Pad8)") (class "Default")
      (node (ref "ADCL") (pin "8") (pinfunction "8_8") (pintype "passive"))
    )
    (net (code "89") (name "unconnected-(COMMUNICATION-Pad1)") (class "Default")
      (node (ref "COMMUNICATION") (pin "1") (pinfunction "1_1") (pintype "passive"))
    )
    (net (code "90") (name "unconnected-(COMMUNICATION-Pad4)") (class "Default")
      (node (ref "COMMUNICATION") (pin "4") (pinfunction "4_4") (pintype "passive"))
    )
    (net (code "91") (name "unconnected-(COMMUNICATION-Pad5)") (class "Default")
      (node (ref "COMMUNICATION") (pin "5") (pinfunction "5_5") (pintype "passive"))
    )
    (net (code "92") (name "unconnected-(COMMUNICATION-Pad6)") (class "Default")
      (node (ref "COMMUNICATION") (pin "6") (pinfunction "6_6") (pintype "passive"))
    )
    (net (code "93") (name "unconnected-(COMMUNICATION-Pad7)") (class "Default")
      (node (ref "COMMUNICATION") (pin "7") (pinfunction "7_7") (pintype "passive"))
    )
    (net (code "94") (name "unconnected-(COMMUNICATION-Pad8)") (class "Default")
      (node (ref "COMMUNICATION") (pin "8") (pinfunction "8_8") (pintype "passive"))
    )
    (net (code "95") (name "unconnected-(JP6-Pad1)") (class "Default")
      (node (ref "JP6") (pin "1") (pinfunction "1_1") (pintype "passive"))
    )
    (net (code "96") (name "unconnected-(JP6-Pad2)") (class "Default")
      (node (ref "JP6") (pin "2") (pinfunction "2_2") (pintype "passive"))
    )
    (net (code "97") (name "unconnected-(POWER-Pad1)") (class "Default")
      (node (ref "POWER") (pin "1") (pinfunction "1_1") (pintype "passive"))
    )
    (net (code "98") (name "unconnected-(POWER-Pad2)") (class "Default")
      (node (ref "POWER") (pin "2") (pinfunction "2_2") (pintype "passive"))
    )
    (net (code "99") (name "unconnected-(POWER-Pad3)") (class "Default")
      (node (ref "POWER") (pin "3") (pinfunction "3_3") (pintype "passive"))
    )
    (net (code "100") (name "unconnected-(POWER-Pad4)") (class "Default")
      (node (ref "POWER") (pin "4") (pinfunction "4_4") (pintype "passive"))
    )
    (net (code "101") (name "unconnected-(POWER-Pad8)") (class "Default")
      (node (ref "POWER") (pin "8") (pinfunction "8_8") (pintype "passive"))
    )
    (net (code "102") (name "unconnected-(R_AUX-PadA)") (class "Default")
      (node (ref "R_AUX") (pin "A") (pinfunction "A_A") (pintype "passive"))
    )
  )
)
